# LEVER-board-production-0.net
KiCad netlist of a schematic drawn in EAGLE
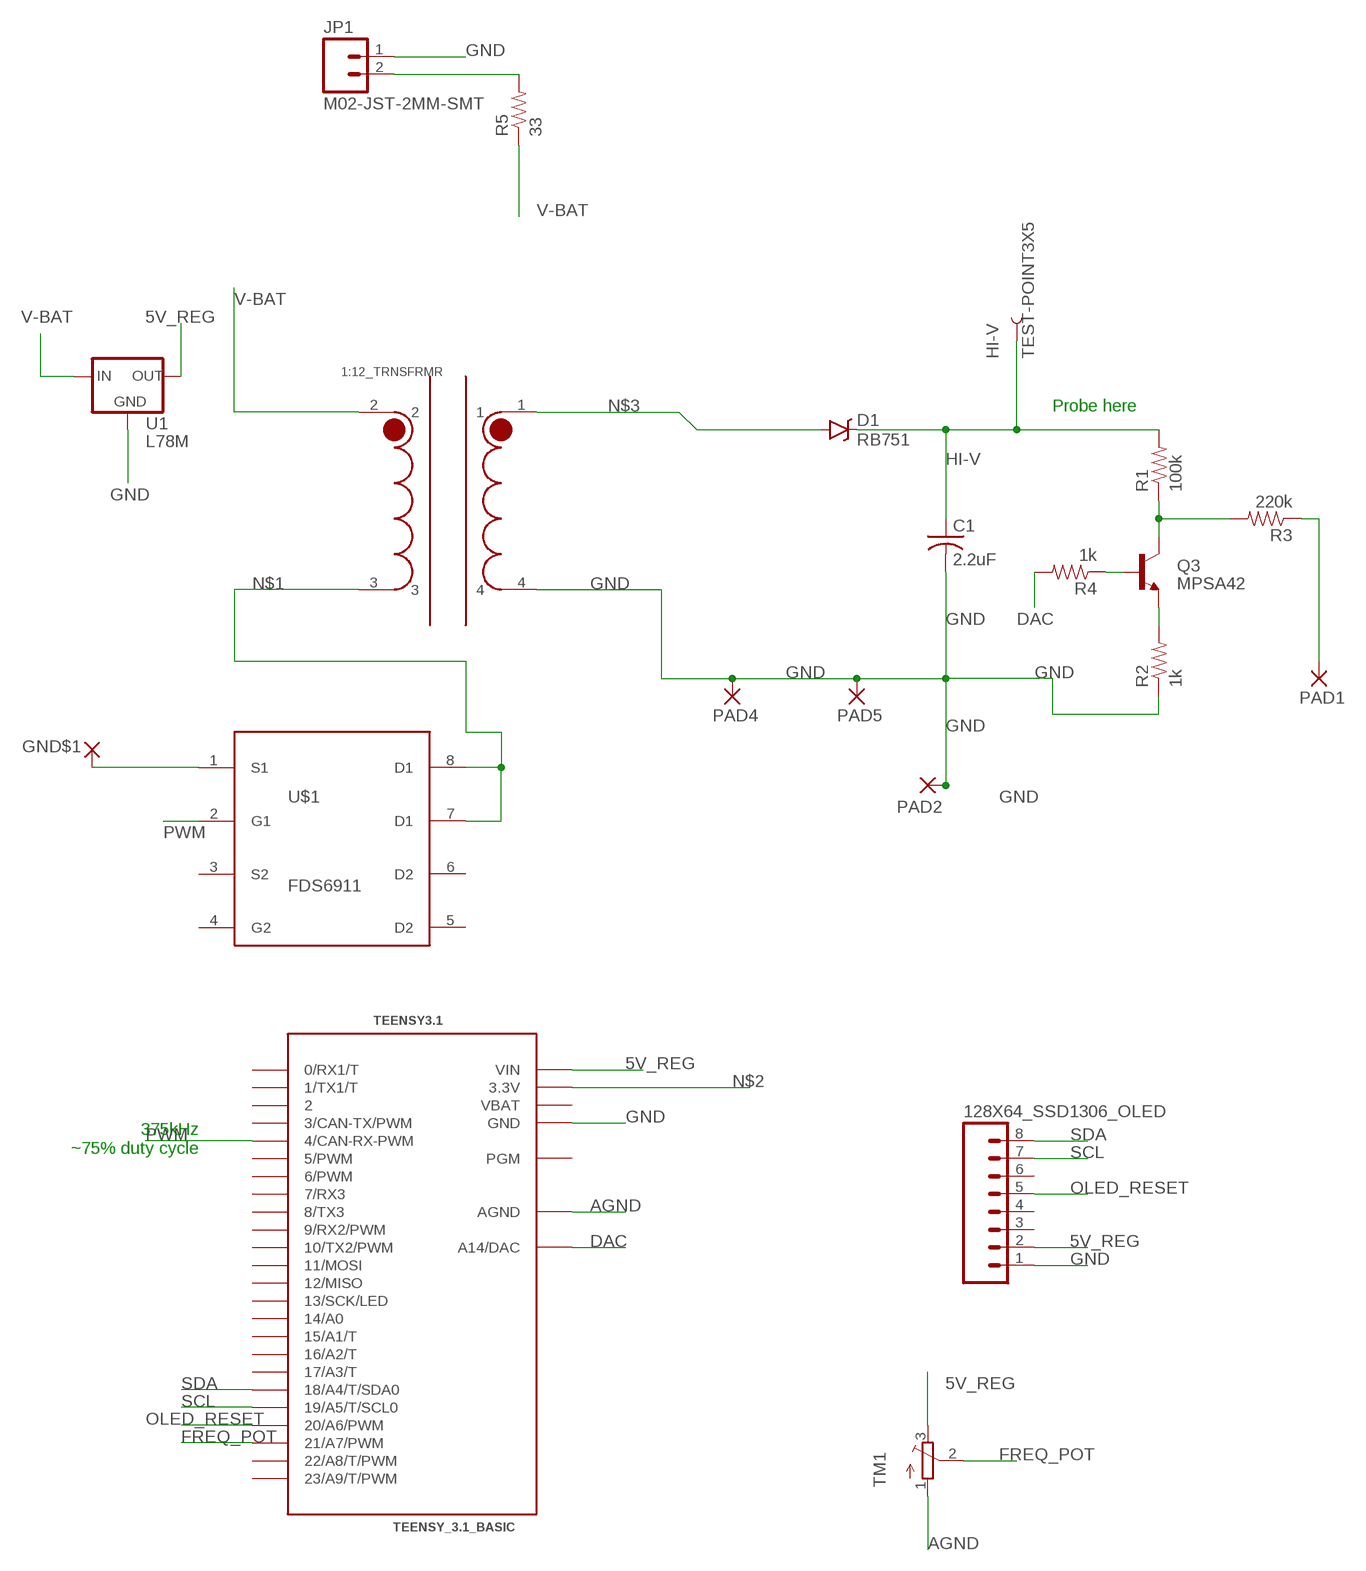
[diagram p0: schematic, sheet 1]

(export (version "E")
  (design (tool "Eeschema 10.0.6"))
  (components
    (comp (ref "1:12_TRNSFRMR")
      (value "PA0367")
      (footprint "eagle-import:PA0367")
      (libsource (lib "eagle-import") (part "PA0367"))
    )
    (comp (ref "128X64_SSD1306_OLED")
      (value "M08LOCK")
      (footprint "eagle-import:1X08_LOCK")
      (libsource (lib "eagle-import") (part "M08LOCK"))
    )
    (comp (ref "C1")
      (value "2.2uF")
      (footprint "eagle-import:C1812")
      (libsource (lib "eagle-import") (part "C-USC1812"))
    )
    (comp (ref "D1")
      (value "RB751")
      (footprint "eagle-import:TO263")
      (libsource (lib "eagle-import") (part "QH03BZ600"))
    )
    (comp (ref "GND$1")
      (value "WIREPADSMD5-2,5")
      (footprint "eagle-import:5-2,5")
      (libsource (lib "eagle-import") (part "WIREPADSMD5-2,5"))
    )
    (comp (ref "HI-V")
      (value "TEST-POINT3X5")
      (footprint "eagle-import:PAD.03X.05")
      (libsource (lib "eagle-import") (part "TEST-POINT3X5"))
    )
    (comp (ref "JP1")
      (value "M02-JST-2MM-SMT")
      (footprint "eagle-import:JST-2-SMD")
      (libsource (lib "eagle-import") (part "M02-JST-2MM-SMT"))
    )
    (comp (ref "PAD1")
      (value "WIREPADSMD5-2,5")
      (footprint "eagle-import:5-2,5")
      (libsource (lib "eagle-import") (part "WIREPADSMD5-2,5"))
    )
    (comp (ref "PAD2")
      (value "WIREPADSMD5-2,5")
      (footprint "eagle-import:5-2,5")
      (libsource (lib "eagle-import") (part "WIREPADSMD5-2,5"))
    )
    (comp (ref "PAD4")
      (value "WIREPADSMD5-2,5")
      (footprint "eagle-import:5-2,5")
      (libsource (lib "eagle-import") (part "WIREPADSMD5-2,5"))
    )
    (comp (ref "PAD5")
      (value "WIREPADSMD5-2,5")
      (footprint "eagle-import:5-2,5")
      (libsource (lib "eagle-import") (part "WIREPADSMD5-2,5"))
    )
    (comp (ref "Q3")
      (value "MPSA42")
      (footprint "eagle-import:TO-92")
      (libsource (lib "eagle-import") (part "TRANSISTOR_NPNP2N2222A"))
    )
    (comp (ref "R1")
      (value "100k")
      (footprint "eagle-import:R2010")
      (libsource (lib "eagle-import") (part "RESISTOR2010"))
    )
    (comp (ref "R2")
      (value "1k")
      (footprint "eagle-import:1206")
      (libsource (lib "eagle-import") (part "RESISTOR1206"))
    )
    (comp (ref "R3")
      (value "220k")
      (footprint "eagle-import:R2010")
      (libsource (lib "eagle-import") (part "RESISTOR2010"))
    )
    (comp (ref "R4")
      (value "1k")
      (footprint "eagle-import:1206")
      (libsource (lib "eagle-import") (part "RESISTOR1206"))
    )
    (comp (ref "R5")
      (value "33")
      (footprint "eagle-import:1206")
      (libsource (lib "eagle-import") (part "RESISTOR1206"))
    )
    (comp (ref "TEENSY3.1")
      (value "TEENSY_3.1_BASIC")
      (footprint "eagle-import:TEENSY_3.1_BASIC")
      (libsource (lib "eagle-import") (part "TEENSY_3.1_BASIC"))
    )
    (comp (ref "TM1")
      (value "TRIMPOT3386")
      (footprint "eagle-import:TRIM-3386")
      (libsource (lib "eagle-import") (part "TRIMPOT3386"))
    )
    (comp (ref "U$1")
      (value "FDS6911")
      (footprint "eagle-import:SO8")
      (libsource (lib "eagle-import") (part "FDS6911"))
    )
    (comp (ref "U1")
      (value "L78M")
      (footprint "eagle-import:DPAK")
      (libsource (lib "eagle-import") (part "L78M"))
    )
  )
  (nets
    (net (code "1") (name "/5V_REG") (class "Default")
      (node (ref "128X64_SSD1306_OLED") (pin "2") (pinfunction "2_2") (pintype "passive"))
      (node (ref "TEENSY3.1") (pin "VIN") (pinfunction "VIN_VIN") (pintype "power_in"))
      (node (ref "TM1") (pin "3") (pinfunction "E_3") (pintype "passive"))
      (node (ref "U1") (pin "3") (pinfunction "OUT_3") (pintype "passive"))
    )
    (net (code "2") (name "/AGND") (class "Default")
      (node (ref "TEENSY3.1") (pin "AGND") (pinfunction "AGND_AGND") (pintype "power_in"))
      (node (ref "TM1") (pin "1") (pinfunction "A_1") (pintype "passive"))
    )
    (net (code "3") (name "/DAC") (class "Default")
      (node (ref "R4") (pin "2") (pinfunction "2_2") (pintype "passive"))
      (node (ref "TEENSY3.1") (pin "A14") (pinfunction "A14/DAC_A14") (pintype "bidirectional"))
    )
    (net (code "4") (name "/FREQ_POT") (class "Default")
      (node (ref "TEENSY3.1") (pin "21/A7") (pinfunction "21/A7/PWM_21/A7") (pintype "bidirectional"))
      (node (ref "TM1") (pin "2") (pinfunction "S_2") (pintype "passive"))
    )
    (net (code "5") (name "/GND") (class "Default")
      (node (ref "128X64_SSD1306_OLED") (pin "1") (pinfunction "1_1") (pintype "passive"))
      (node (ref "1:12_TRNSFRMR") (pin "4") (pinfunction "4_4") (pintype "bidirectional"))
      (node (ref "C1") (pin "2") (pinfunction "2_2") (pintype "passive"))
      (node (ref "GND$1") (pin "1") (pinfunction "P_1") (pintype "passive"))
      (node (ref "JP1") (pin "1") (pinfunction "2_1") (pintype "passive"))
      (node (ref "PAD2") (pin "1") (pinfunction "P_1") (pintype "passive"))
      (node (ref "PAD4") (pin "1") (pinfunction "P_1") (pintype "passive"))
      (node (ref "PAD5") (pin "1") (pinfunction "P_1") (pintype "passive"))
      (node (ref "R2") (pin "1") (pinfunction "1_1") (pintype "passive"))
      (node (ref "TEENSY3.1") (pin "GND") (pinfunction "GND_GND") (pintype "power_in"))
      (node (ref "TEENSY3.1") (pin "GND1") (pinfunction "GND_GND1") (pintype "power_in"))
      (node (ref "U$1") (pin "1") (pinfunction "S1_1") (pintype "bidirectional"))
      (node (ref "U1") (pin "4") (pinfunction "GND_4") (pintype "input"))
    )
    (net (code "6") (name "/HI-V") (class "Default")
      (node (ref "C1") (pin "1") (pinfunction "1_1") (pintype "passive"))
      (node (ref "D1") (pin "1") (pinfunction "C_1") (pintype "passive"))
      (node (ref "HI-V") (pin "P$1") (pinfunction "1_P$1") (pintype "bidirectional"))
      (node (ref "R1") (pin "2") (pinfunction "2_2") (pintype "passive"))
    )
    (net (code "7") (name "/N$1") (class "Default")
      (node (ref "1:12_TRNSFRMR") (pin "3") (pinfunction "3_3") (pintype "bidirectional"))
      (node (ref "U$1") (pin "7") (pinfunction "D1_7") (pintype "bidirectional"))
      (node (ref "U$1") (pin "8") (pinfunction "D1_8") (pintype "bidirectional"))
    )
    (net (code "8") (name "/N$2") (class "Default")
      (node (ref "TEENSY3.1") (pin "3.3V") (pinfunction "3.3V_3.3V") (pintype "power_in"))
      (node (ref "TEENSY3.1") (pin "3.3V1") (pinfunction "3.3V_3.3V1") (pintype "power_in"))
    )
    (net (code "9") (name "/N$3") (class "Default")
      (node (ref "1:12_TRNSFRMR") (pin "1") (pinfunction "1_1") (pintype "bidirectional"))
      (node (ref "D1") (pin "2") (pinfunction "A_2") (pintype "passive"))
    )
    (net (code "10") (name "/OLED_RESET") (class "Default")
      (node (ref "128X64_SSD1306_OLED") (pin "5") (pinfunction "5_5") (pintype "passive"))
      (node (ref "TEENSY3.1") (pin "20/A6") (pinfunction "20/A6/PWM_20/A6") (pintype "bidirectional"))
    )
    (net (code "11") (name "/PWM") (class "Default")
      (node (ref "TEENSY3.1") (pin "4") (pinfunction "4/CAN-RX-PWM_4") (pintype "bidirectional"))
      (node (ref "U$1") (pin "2") (pinfunction "G1_2") (pintype "bidirectional"))
    )
    (net (code "12") (name "/SCL") (class "Default")
      (node (ref "128X64_SSD1306_OLED") (pin "7") (pinfunction "7_7") (pintype "passive"))
      (node (ref "TEENSY3.1") (pin "19/A5") (pinfunction "19/A5/T/SCL0_19/A5") (pintype "bidirectional"))
    )
    (net (code "13") (name "/SDA") (class "Default")
      (node (ref "128X64_SSD1306_OLED") (pin "8") (pinfunction "8_8") (pintype "passive"))
      (node (ref "TEENSY3.1") (pin "18/A4") (pinfunction "18/A4/T/SDA0_18/A4") (pintype "bidirectional"))
    )
    (net (code "14") (name "/V-BAT") (class "Default")
      (node (ref "1:12_TRNSFRMR") (pin "2") (pinfunction "2_2") (pintype "bidirectional"))
      (node (ref "R5") (pin "1") (pinfunction "1_1") (pintype "passive"))
      (node (ref "U1") (pin "1") (pinfunction "IN_1") (pintype "input"))
    )
    (net (code "15") (name "/VBAT") (class "Default")
      (node (ref "TEENSY3.1") (pin "VBAT") (pinfunction "VBAT_VBAT") (pintype "power_in"))
    )
    (net (code "16") (name "Net-(JP1-1)") (class "Default")
      (node (ref "JP1") (pin "2") (pinfunction "1_2") (pintype "passive"))
      (node (ref "R5") (pin "2") (pinfunction "2_2") (pintype "passive"))
    )
    (net (code "17") (name "Net-(PAD1-P)") (class "Default")
      (node (ref "PAD1") (pin "1") (pinfunction "P_1") (pintype "passive"))
      (node (ref "R3") (pin "1") (pinfunction "1_1") (pintype "passive"))
    )
    (net (code "18") (name "Net-(Q3-B)") (class "Default")
      (node (ref "Q3") (pin "2") (pinfunction "B_2") (pintype "passive"))
      (node (ref "R4") (pin "1") (pinfunction "1_1") (pintype "passive"))
    )
    (net (code "19") (name "Net-(Q3-C)") (class "Default")
      (node (ref "Q3") (pin "1") (pinfunction "C_1") (pintype "passive"))
      (node (ref "R1") (pin "1") (pinfunction "1_1") (pintype "passive"))
      (node (ref "R3") (pin "2") (pinfunction "2_2") (pintype "passive"))
    )
    (net (code "20") (name "Net-(Q3-E)") (class "Default")
      (node (ref "Q3") (pin "3") (pinfunction "E_3") (pintype "passive"))
      (node (ref "R2") (pin "2") (pinfunction "2_2") (pintype "passive"))
    )
    (net (code "21") (name "unconnected-(128X64_SSD1306_OLED-Pad3)") (class "Default")
      (node (ref "128X64_SSD1306_OLED") (pin "3") (pinfunction "3_3") (pintype "passive"))
    )
    (net (code "22") (name "unconnected-(128X64_SSD1306_OLED-Pad4)") (class "Default")
      (node (ref "128X64_SSD1306_OLED") (pin "4") (pinfunction "4_4") (pintype "passive"))
    )
    (net (code "23") (name "unconnected-(128X64_SSD1306_OLED-Pad6)") (class "Default")
      (node (ref "128X64_SSD1306_OLED") (pin "6") (pinfunction "6_6") (pintype "passive"))
    )
    (net (code "24") (name "unconnected-(TEENSY3.1-0{slash}RX1{slash}T-Pad0)") (class "Default")
      (node (ref "TEENSY3.1") (pin "0") (pinfunction "0/RX1/T_0") (pintype "bidirectional"))
    )
    (net (code "25") (name "unconnected-(TEENSY3.1-1{slash}TX1{slash}T-Pad1)") (class "Default")
      (node (ref "TEENSY3.1") (pin "1") (pinfunction "1/TX1/T_1") (pintype "bidirectional"))
    )
    (net (code "26") (name "unconnected-(TEENSY3.1-3{slash}CAN-TX{slash}PWM-Pad3)") (class "Default")
      (node (ref "TEENSY3.1") (pin "3") (pinfunction "3/CAN-TX/PWM_3") (pintype "bidirectional"))
    )
    (net (code "27") (name "unconnected-(TEENSY3.1-5{slash}PWM-Pad5)") (class "Default")
      (node (ref "TEENSY3.1") (pin "5") (pinfunction "5/PWM_5") (pintype "bidirectional"))
    )
    (net (code "28") (name "unconnected-(TEENSY3.1-6{slash}PWM-Pad6)") (class "Default")
      (node (ref "TEENSY3.1") (pin "6") (pinfunction "6/PWM_6") (pintype "bidirectional"))
    )
    (net (code "29") (name "unconnected-(TEENSY3.1-7{slash}RX3-Pad7)") (class "Default")
      (node (ref "TEENSY3.1") (pin "7") (pinfunction "7/RX3_7") (pintype "bidirectional"))
    )
    (net (code "30") (name "unconnected-(TEENSY3.1-8{slash}TX3-Pad8)") (class "Default")
      (node (ref "TEENSY3.1") (pin "8") (pinfunction "8/TX3_8") (pintype "bidirectional"))
    )
    (net (code "31") (name "unconnected-(TEENSY3.1-9{slash}RX2{slash}PWM-Pad9)") (class "Default")
      (node (ref "TEENSY3.1") (pin "9") (pinfunction "9/RX2/PWM_9") (pintype "bidirectional"))
    )
    (net (code "32") (name "unconnected-(TEENSY3.1-10{slash}TX2{slash}PWM-Pad10)") (class "Default")
      (node (ref "TEENSY3.1") (pin "10") (pinfunction "10/TX2/PWM_10") (pintype "bidirectional"))
    )
    (net (code "33") (name "unconnected-(TEENSY3.1-11{slash}MOSI-Pad11)") (class "Default")
      (node (ref "TEENSY3.1") (pin "11") (pinfunction "11/MOSI_11") (pintype "bidirectional"))
    )
    (net (code "34") (name "unconnected-(TEENSY3.1-12{slash}MISO-Pad12)") (class "Default")
      (node (ref "TEENSY3.1") (pin "12") (pinfunction "12/MISO_12") (pintype "bidirectional"))
    )
    (net (code "35") (name "unconnected-(TEENSY3.1-13{slash}SCK{slash}LED-Pad13)") (class "Default")
      (node (ref "TEENSY3.1") (pin "13") (pinfunction "13/SCK/LED_13") (pintype "bidirectional"))
    )
    (net (code "36") (name "unconnected-(TEENSY3.1-15{slash}A1{slash}T-Pad15{slash}A1)") (class "Default")
      (node (ref "TEENSY3.1") (pin "15/A1") (pinfunction "15/A1/T_15/A1") (pintype "bidirectional"))
    )
    (net (code "37") (name "unconnected-(TEENSY3.1-16{slash}A2{slash}T-Pad16{slash}A2)") (class "Default")
      (node (ref "TEENSY3.1") (pin "16/A2") (pinfunction "16/A2/T_16/A2") (pintype "bidirectional"))
    )
    (net (code "38") (name "unconnected-(TEENSY3.1-17{slash}A3{slash}T-Pad17{slash}A3)") (class "Default")
      (node (ref "TEENSY3.1") (pin "17/A3") (pinfunction "17/A3/T_17/A3") (pintype "bidirectional"))
    )
    (net (code "39") (name "unconnected-(TEENSY3.1-22{slash}A8{slash}T{slash}PWM-Pad22{slash}A8)") (class "Default")
      (node (ref "TEENSY3.1") (pin "22/A8") (pinfunction "22/A8/T/PWM_22/A8") (pintype "bidirectional"))
    )
    (net (code "40") (name "unconnected-(TEENSY3.1-23{slash}A9{slash}T{slash}PWM-Pad23{slash}A9)") (class "Default")
      (node (ref "TEENSY3.1") (pin "23/A9") (pinfunction "23/A9/T/PWM_23/A9") (pintype "bidirectional"))
    )
    (net (code "41") (name "unconnected-(TEENSY3.1-Pad2)") (class "Default")
      (node (ref "TEENSY3.1") (pin "2") (pinfunction "2_2") (pintype "bidirectional"))
    )
    (net (code "42") (name "unconnected-(TEENSY3.1-Pad14{slash}A0)") (class "Default")
      (node (ref "TEENSY3.1") (pin "14/A0") (pinfunction "14/A0_14/A0") (pintype "bidirectional"))
    )
    (net (code "43") (name "unconnected-(TEENSY3.1-PadPGM)") (class "Default")
      (node (ref "TEENSY3.1") (pin "PGM") (pinfunction "PGM_PGM") (pintype "bidirectional"))
    )
    (net (code "44") (name "unconnected-(U$1-D2-Pad5)") (class "Default")
      (node (ref "U$1") (pin "5") (pinfunction "D2_5") (pintype "bidirectional"))
    )
    (net (code "45") (name "unconnected-(U$1-D2-Pad6)") (class "Default")
      (node (ref "U$1") (pin "6") (pinfunction "D2_6") (pintype "bidirectional"))
    )
    (net (code "46") (name "unconnected-(U$1-G2-Pad4)") (class "Default")
      (node (ref "U$1") (pin "4") (pinfunction "G2_4") (pintype "bidirectional"))
    )
    (net (code "47") (name "unconnected-(U$1-S2-Pad3)") (class "Default")
      (node (ref "U$1") (pin "3") (pinfunction "S2_3") (pintype "bidirectional"))
    )
  )
)
